# ARC.net
KiCad netlist of a schematic drawn in Altium Designer
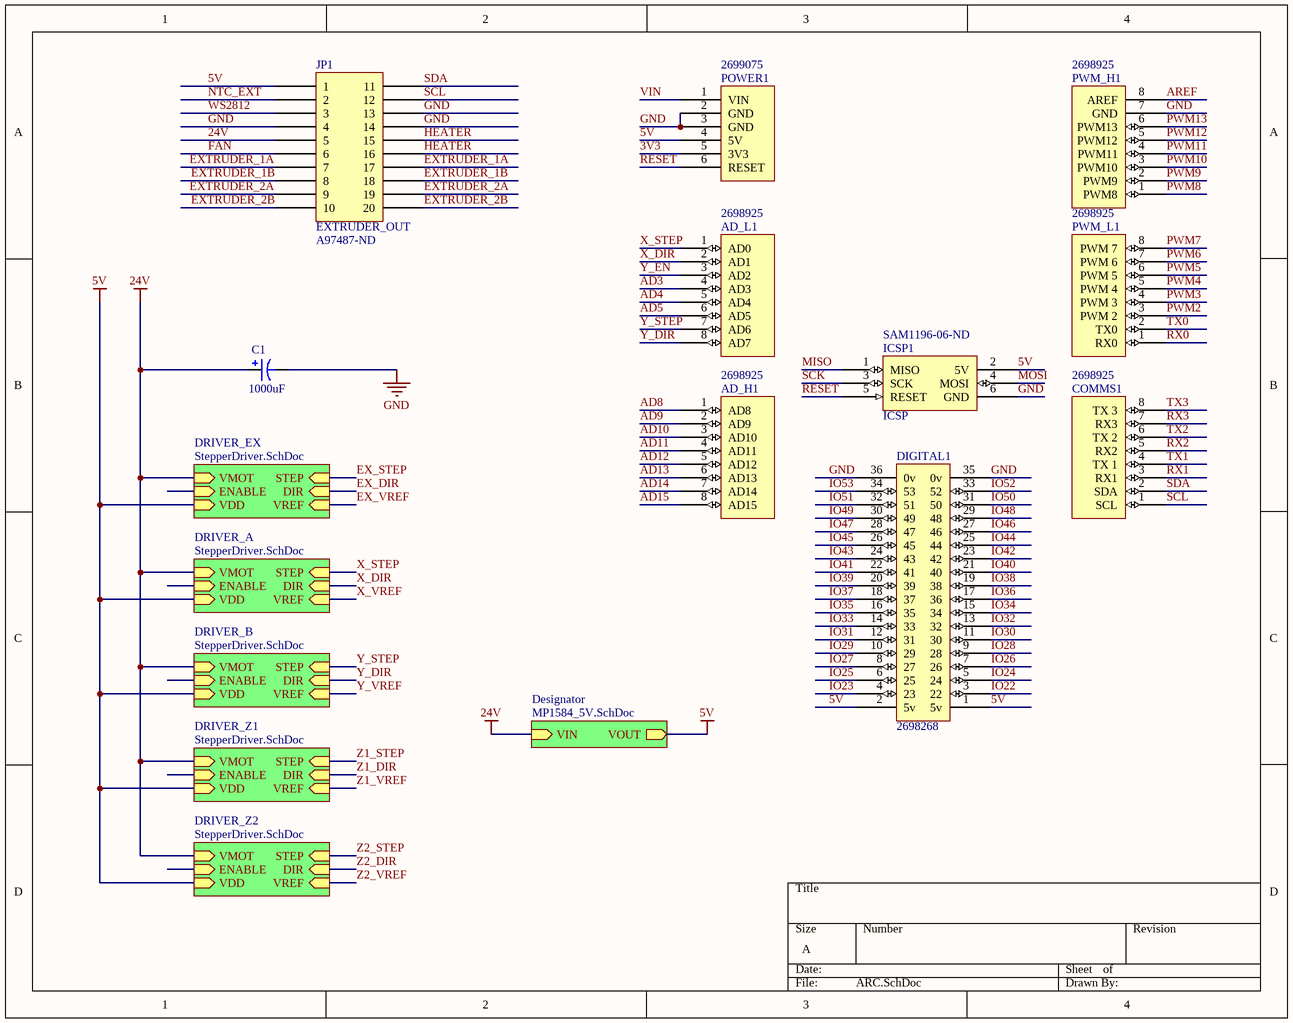
[diagram p0: ARC.SchDoc]

(export (version "E")
  (design (tool "Eeschema 10.0.6"))
  (components
    (comp (ref "AD_H1")
      (value "AD_H")
      (footprint "Header 8x1 8.5mm")
      (fields (field (name "SUPPLIER PART NUMBER 4") "2698925"))
      (libsource (lib "Header") (part "AD_H"))
    )
    (comp (ref "AD_L1")
      (value "AD_L")
      (footprint "Header 8x1 8.5mm")
      (fields (field (name "SUPPLIER PART NUMBER 5") "2698925"))
      (libsource (lib "Header") (part "AD_L"))
    )
    (comp (ref "C1")
      (value "1000uF")
      (footprint "CAP_12.5mm")
      (description "Generic electrolytic capacitor w/ 12.5mm diameter and 5mm pitch")
      (libsource (lib "Components") (part "CAP_12.5MM_GENERIC"))
    )
    (comp (ref "COMMS1")
      (value "Communication")
      (footprint "Header 8x1 8.5mm")
      (fields (field (name "SUPPLIER PART NUMBER 4") "2698925"))
      (libsource (lib "Header") (part "Communication"))
    )
    (comp (ref "DIGITAL1")
      (value "IO_36")
      (footprint "HEADER 36X 8MM")
      (fields (field (name "SUPPLIER PART NUMBER 5") "2698268"))
      (libsource (lib "Header") (part "IO_36"))
    )
    (comp (ref "ICSP1")
      (value "ICSP")
      (footprint "ICSP")
      (fields (field (name "SUPPLIER PART NUMBER 5") "SAM1196-06-ND"))
      (libsource (lib "Header") (part "ICSP"))
    )
    (comp (ref "JP1")
      (value "EXTRUDER_OUT")
      (footprint "IDC20")
      (fields (field (name "SUPPLIER PART NUMBER 1") "A97487-ND"))
      (libsource (lib "Header") (part "IDC20"))
    )
    (comp (ref "POWER1")
      (value "POWER")
      (footprint "Header 6x1 8.5mm")
      (fields (field (name "SUPPLIER PART NUMBER 2") "2699075"))
      (libsource (lib "Header") (part "POWER"))
    )
    (comp (ref "PWM_H1")
      (value "PWM_H")
      (footprint "Header 8x1 8.5mm")
      (fields (field (name "SUPPLIER PART NUMBER 4") "2698925"))
      (libsource (lib "Header") (part "PWM_H"))
    )
    (comp (ref "PWM_L1")
      (value "PWM_L")
      (footprint "Header 8x1 8.5mm")
      (fields (field (name "SUPPLIER PART NUMBER 4") "2698925"))
      (libsource (lib "Header") (part "PWM_L"))
    )
  )
  (nets
    (net (code "1") (name "/3V3") (class "Default")
      (node (ref "POWER1") (pin "5") (pinfunction "3V3_5") (pintype "power_in"))
    )
    (net (code "2") (name "/AD3") (class "Default")
      (node (ref "AD_L1") (pin "4") (pinfunction "AD3_4") (pintype "bidirectional"))
    )
    (net (code "3") (name "/AD4") (class "Default")
      (node (ref "AD_L1") (pin "5") (pinfunction "AD4_5") (pintype "bidirectional"))
    )
    (net (code "4") (name "/AD5") (class "Default")
      (node (ref "AD_L1") (pin "6") (pinfunction "AD5_6") (pintype "bidirectional"))
    )
    (net (code "5") (name "/AD8") (class "Default")
      (node (ref "AD_H1") (pin "1") (pinfunction "AD8_1") (pintype "bidirectional"))
    )
    (net (code "6") (name "/AD9") (class "Default")
      (node (ref "AD_H1") (pin "2") (pinfunction "AD9_2") (pintype "bidirectional"))
    )
    (net (code "7") (name "/AD10") (class "Default")
      (node (ref "AD_H1") (pin "3") (pinfunction "AD10_3") (pintype "bidirectional"))
    )
    (net (code "8") (name "/AD11") (class "Default")
      (node (ref "AD_H1") (pin "4") (pinfunction "AD11_4") (pintype "bidirectional"))
    )
    (net (code "9") (name "/AD12") (class "Default")
      (node (ref "AD_H1") (pin "5") (pinfunction "AD12_5") (pintype "bidirectional"))
    )
    (net (code "10") (name "/AD13") (class "Default")
      (node (ref "AD_H1") (pin "6") (pinfunction "AD13_6") (pintype "bidirectional"))
    )
    (net (code "11") (name "/AD14") (class "Default")
      (node (ref "AD_H1") (pin "7") (pinfunction "AD14_7") (pintype "bidirectional"))
    )
    (net (code "12") (name "/AD15") (class "Default")
      (node (ref "AD_H1") (pin "8") (pinfunction "AD15_8") (pintype "bidirectional"))
    )
    (net (code "13") (name "/AREF") (class "Default")
      (node (ref "PWM_H1") (pin "8") (pinfunction "AREF_8") (pintype "passive"))
    )
    (net (code "19") (name "/EXTRUDER_1A") (class "Default")
      (node (ref "JP1") (pin "17") (pinfunction "17_17") (pintype "passive"))
      (node (ref "JP1") (pin "7") (pinfunction "7_7") (pintype "passive"))
    )
    (net (code "20") (name "/EXTRUDER_1B") (class "Default")
      (node (ref "JP1") (pin "18") (pinfunction "18_18") (pintype "passive"))
      (node (ref "JP1") (pin "8") (pinfunction "8_8") (pintype "passive"))
    )
    (net (code "21") (name "/EXTRUDER_2A") (class "Default")
      (node (ref "JP1") (pin "19") (pinfunction "19_19") (pintype "passive"))
      (node (ref "JP1") (pin "9") (pinfunction "9_9") (pintype "passive"))
    )
    (net (code "22") (name "/EXTRUDER_2B") (class "Default")
      (node (ref "JP1") (pin "10") (pinfunction "10_10") (pintype "passive"))
      (node (ref "JP1") (pin "20") (pinfunction "20_20") (pintype "passive"))
    )
    (net (code "26") (name "/FAN") (class "Default")
      (node (ref "JP1") (pin "6") (pinfunction "6_6") (pintype "passive"))
    )
    (net (code "27") (name "/HEATER") (class "Default")
      (node (ref "JP1") (pin "15") (pinfunction "15_15") (pintype "passive"))
      (node (ref "JP1") (pin "16") (pinfunction "16_16") (pintype "passive"))
    )
    (net (code "28") (name "/IO22") (class "Default")
      (node (ref "DIGITAL1") (pin "3") (pinfunction "22_3") (pintype "bidirectional"))
    )
    (net (code "29") (name "/IO23") (class "Default")
      (node (ref "DIGITAL1") (pin "4") (pinfunction "23_4") (pintype "bidirectional"))
    )
    (net (code "30") (name "/IO24") (class "Default")
      (node (ref "DIGITAL1") (pin "5") (pinfunction "24_5") (pintype "bidirectional"))
    )
    (net (code "31") (name "/IO25") (class "Default")
      (node (ref "DIGITAL1") (pin "6") (pinfunction "25_6") (pintype "bidirectional"))
    )
    (net (code "32") (name "/IO26") (class "Default")
      (node (ref "DIGITAL1") (pin "7") (pinfunction "26_7") (pintype "bidirectional"))
    )
    (net (code "33") (name "/IO27") (class "Default")
      (node (ref "DIGITAL1") (pin "8") (pinfunction "27_8") (pintype "bidirectional"))
    )
    (net (code "34") (name "/IO28") (class "Default")
      (node (ref "DIGITAL1") (pin "9") (pinfunction "28_9") (pintype "bidirectional"))
    )
    (net (code "35") (name "/IO29") (class "Default")
      (node (ref "DIGITAL1") (pin "10") (pinfunction "29_10") (pintype "bidirectional"))
    )
    (net (code "36") (name "/IO30") (class "Default")
      (node (ref "DIGITAL1") (pin "11") (pinfunction "30_11") (pintype "bidirectional"))
    )
    (net (code "37") (name "/IO31") (class "Default")
      (node (ref "DIGITAL1") (pin "12") (pinfunction "31_12") (pintype "bidirectional"))
    )
    (net (code "38") (name "/IO32") (class "Default")
      (node (ref "DIGITAL1") (pin "13") (pinfunction "32_13") (pintype "bidirectional"))
    )
    (net (code "39") (name "/IO33") (class "Default")
      (node (ref "DIGITAL1") (pin "14") (pinfunction "33_14") (pintype "bidirectional"))
    )
    (net (code "40") (name "/IO34") (class "Default")
      (node (ref "DIGITAL1") (pin "15") (pinfunction "34_15") (pintype "bidirectional"))
    )
    (net (code "41") (name "/IO35") (class "Default")
      (node (ref "DIGITAL1") (pin "16") (pinfunction "35_16") (pintype "bidirectional"))
    )
    (net (code "42") (name "/IO36") (class "Default")
      (node (ref "DIGITAL1") (pin "17") (pinfunction "36_17") (pintype "bidirectional"))
    )
    (net (code "43") (name "/IO37") (class "Default")
      (node (ref "DIGITAL1") (pin "18") (pinfunction "37_18") (pintype "bidirectional"))
    )
    (net (code "44") (name "/IO38") (class "Default")
      (node (ref "DIGITAL1") (pin "19") (pinfunction "38_19") (pintype "bidirectional"))
    )
    (net (code "45") (name "/IO39") (class "Default")
      (node (ref "DIGITAL1") (pin "20") (pinfunction "39_20") (pintype "bidirectional"))
    )
    (net (code "46") (name "/IO40") (class "Default")
      (node (ref "DIGITAL1") (pin "21") (pinfunction "40_21") (pintype "bidirectional"))
    )
    (net (code "47") (name "/IO41") (class "Default")
      (node (ref "DIGITAL1") (pin "22") (pinfunction "41_22") (pintype "bidirectional"))
    )
    (net (code "48") (name "/IO42") (class "Default")
      (node (ref "DIGITAL1") (pin "23") (pinfunction "42_23") (pintype "bidirectional"))
    )
    (net (code "49") (name "/IO43") (class "Default")
      (node (ref "DIGITAL1") (pin "24") (pinfunction "43_24") (pintype "bidirectional"))
    )
    (net (code "50") (name "/IO44") (class "Default")
      (node (ref "DIGITAL1") (pin "25") (pinfunction "44_25") (pintype "bidirectional"))
    )
    (net (code "51") (name "/IO45") (class "Default")
      (node (ref "DIGITAL1") (pin "26") (pinfunction "45_26") (pintype "bidirectional"))
    )
    (net (code "52") (name "/IO46") (class "Default")
      (node (ref "DIGITAL1") (pin "27") (pinfunction "46_27") (pintype "bidirectional"))
    )
    (net (code "53") (name "/IO47") (class "Default")
      (node (ref "DIGITAL1") (pin "28") (pinfunction "47_28") (pintype "bidirectional"))
    )
    (net (code "54") (name "/IO48") (class "Default")
      (node (ref "DIGITAL1") (pin "29") (pinfunction "48_29") (pintype "bidirectional"))
    )
    (net (code "55") (name "/IO49") (class "Default")
      (node (ref "DIGITAL1") (pin "30") (pinfunction "49_30") (pintype "bidirectional"))
    )
    (net (code "56") (name "/IO50") (class "Default")
      (node (ref "DIGITAL1") (pin "31") (pinfunction "50_31") (pintype "bidirectional"))
    )
    (net (code "57") (name "/IO51") (class "Default")
      (node (ref "DIGITAL1") (pin "32") (pinfunction "51_32") (pintype "bidirectional"))
    )
    (net (code "58") (name "/IO52") (class "Default")
      (node (ref "DIGITAL1") (pin "33") (pinfunction "52_33") (pintype "bidirectional"))
    )
    (net (code "59") (name "/IO53") (class "Default")
      (node (ref "DIGITAL1") (pin "34") (pinfunction "53_34") (pintype "bidirectional"))
    )
    (net (code "60") (name "/MISO") (class "Default")
      (node (ref "ICSP1") (pin "1") (pinfunction "MISO_1") (pintype "bidirectional"))
    )
    (net (code "61") (name "/MOSI") (class "Default")
      (node (ref "ICSP1") (pin "4") (pinfunction "MOSI_4") (pintype "bidirectional"))
    )
    (net (code "62") (name "/NTC_EXT") (class "Default")
      (node (ref "JP1") (pin "2") (pinfunction "2_2") (pintype "passive"))
    )
    (net (code "63") (name "/PWM2") (class "Default")
      (node (ref "PWM_L1") (pin "3") (pinfunction "PWM_2_3") (pintype "bidirectional"))
    )
    (net (code "64") (name "/PWM3") (class "Default")
      (node (ref "PWM_L1") (pin "4") (pinfunction "PWM_3_4") (pintype "bidirectional"))
    )
    (net (code "65") (name "/PWM4") (class "Default")
      (node (ref "PWM_L1") (pin "5") (pinfunction "PWM_4_5") (pintype "bidirectional"))
    )
    (net (code "66") (name "/PWM5") (class "Default")
      (node (ref "PWM_L1") (pin "6") (pinfunction "PWM_5_6") (pintype "bidirectional"))
    )
    (net (code "67") (name "/PWM6") (class "Default")
      (node (ref "PWM_L1") (pin "7") (pinfunction "PWM_6_7") (pintype "bidirectional"))
    )
    (net (code "68") (name "/PWM7") (class "Default")
      (node (ref "PWM_L1") (pin "8") (pinfunction "PWM_7_8") (pintype "bidirectional"))
    )
    (net (code "69") (name "/PWM8") (class "Default")
      (node (ref "PWM_H1") (pin "1") (pinfunction "PWM8_1") (pintype "bidirectional"))
    )
    (net (code "70") (name "/PWM9") (class "Default")
      (node (ref "PWM_H1") (pin "2") (pinfunction "PWM9_2") (pintype "bidirectional"))
    )
    (net (code "71") (name "/PWM10") (class "Default")
      (node (ref "PWM_H1") (pin "3") (pinfunction "PWM10_3") (pintype "bidirectional"))
    )
    (net (code "72") (name "/PWM11") (class "Default")
      (node (ref "PWM_H1") (pin "4") (pinfunction "PWM11_4") (pintype "bidirectional"))
    )
    (net (code "73") (name "/PWM12") (class "Default")
      (node (ref "PWM_H1") (pin "5") (pinfunction "PWM12_5") (pintype "bidirectional"))
    )
    (net (code "74") (name "/PWM13") (class "Default")
      (node (ref "PWM_H1") (pin "6") (pinfunction "PWM13_6") (pintype "bidirectional"))
    )
    (net (code "75") (name "/RESET") (class "Default")
      (node (ref "ICSP1") (pin "5") (pinfunction "RESET_5") (pintype "input"))
      (node (ref "POWER1") (pin "6") (pinfunction "RESET_6") (pintype "passive"))
    )
    (net (code "76") (name "/RX0") (class "Default")
      (node (ref "PWM_L1") (pin "1") (pinfunction "RX0_1") (pintype "bidirectional"))
    )
    (net (code "77") (name "/RX1") (class "Default")
      (node (ref "COMMS1") (pin "3") (pinfunction "RX1_3") (pintype "bidirectional"))
    )
    (net (code "78") (name "/RX2") (class "Default")
      (node (ref "COMMS1") (pin "5") (pinfunction "RX2_5") (pintype "bidirectional"))
    )
    (net (code "79") (name "/RX3") (class "Default")
      (node (ref "COMMS1") (pin "7") (pinfunction "RX3_7") (pintype "bidirectional"))
    )
    (net (code "80") (name "/SCK") (class "Default")
      (node (ref "ICSP1") (pin "3") (pinfunction "SCK_3") (pintype "bidirectional"))
    )
    (net (code "81") (name "/SCL") (class "Default")
      (node (ref "COMMS1") (pin "1") (pinfunction "SCL_1") (pintype "bidirectional"))
      (node (ref "JP1") (pin "12") (pinfunction "12_12") (pintype "passive"))
    )
    (net (code "82") (name "/SDA") (class "Default")
      (node (ref "COMMS1") (pin "2") (pinfunction "SDA_2") (pintype "bidirectional"))
      (node (ref "JP1") (pin "11") (pinfunction "11_11") (pintype "passive"))
    )
    (net (code "83") (name "/TX0") (class "Default")
      (node (ref "PWM_L1") (pin "2") (pinfunction "TX0_2") (pintype "bidirectional"))
    )
    (net (code "84") (name "/TX1") (class "Default")
      (node (ref "COMMS1") (pin "4") (pinfunction "TX_1_4") (pintype "bidirectional"))
    )
    (net (code "85") (name "/TX2") (class "Default")
      (node (ref "COMMS1") (pin "6") (pinfunction "TX_2_6") (pintype "bidirectional"))
    )
    (net (code "86") (name "/TX3") (class "Default")
      (node (ref "COMMS1") (pin "8") (pinfunction "TX_3_8") (pintype "bidirectional"))
    )
    (net (code "87") (name "/VIN") (class "Default")
      (node (ref "POWER1") (pin "1") (pinfunction "VIN_1") (pintype "power_in"))
    )
    (net (code "88") (name "/WS2812") (class "Default")
      (node (ref "JP1") (pin "3") (pinfunction "3_3") (pintype "passive"))
    )
    (net (code "89") (name "/X_DIR") (class "Default")
      (node (ref "AD_L1") (pin "2") (pinfunction "AD1_2") (pintype "bidirectional"))
    )
    (net (code "90") (name "/X_STEP") (class "Default")
      (node (ref "AD_L1") (pin "1") (pinfunction "AD0_1") (pintype "bidirectional"))
    )
    (net (code "92") (name "/Y_DIR") (class "Default")
      (node (ref "AD_L1") (pin "8") (pinfunction "AD7_8") (pintype "bidirectional"))
    )
    (net (code "93") (name "/Y_EN") (class "Default")
      (node (ref "AD_L1") (pin "3") (pinfunction "AD2_3") (pintype "bidirectional"))
    )
    (net (code "94") (name "/Y_STEP") (class "Default")
      (node (ref "AD_L1") (pin "7") (pinfunction "AD6_7") (pintype "bidirectional"))
    )
    (net (code "102") (name "5V") (class "Default")
      (node (ref "DIGITAL1") (pin "1") (pinfunction "5v_1") (pintype "power_in"))
      (node (ref "DIGITAL1") (pin "2") (pinfunction "5v_2") (pintype "power_in"))
      (node (ref "ICSP1") (pin "2") (pinfunction "5V_2") (pintype "power_in"))
      (node (ref "JP1") (pin "1") (pinfunction "1_1") (pintype "passive"))
      (node (ref "POWER1") (pin "4") (pinfunction "5V_4") (pintype "power_in"))
    )
    (net (code "103") (name "24V") (class "Default")
      (node (ref "C1") (pin "0") (pinfunction "0_0") (pintype "passive"))
      (node (ref "JP1") (pin "5") (pinfunction "5_5") (pintype "passive"))
    )
    (net (code "104") (name "GND") (class "Default")
      (node (ref "C1") (pin "1") (pinfunction "1_1") (pintype "passive"))
      (node (ref "DIGITAL1") (pin "35") (pinfunction "0v_35") (pintype "power_in"))
      (node (ref "DIGITAL1") (pin "36") (pinfunction "0v_36") (pintype "power_in"))
      (node (ref "ICSP1") (pin "6") (pinfunction "GND_6") (pintype "power_in"))
      (node (ref "JP1") (pin "13") (pinfunction "13_13") (pintype "passive"))
      (node (ref "JP1") (pin "14") (pinfunction "14_14") (pintype "passive"))
      (node (ref "JP1") (pin "4") (pinfunction "4_4") (pintype "passive"))
      (node (ref "POWER1") (pin "2") (pinfunction "GND_2") (pintype "power_in"))
      (node (ref "POWER1") (pin "3") (pinfunction "GND_3") (pintype "power_in"))
      (node (ref "PWM_H1") (pin "7") (pinfunction "GND_7") (pintype "power_in"))
    )
  )
)
